# RingEncoder.net
KiCad netlist of a schematic drawn in Altium Designer
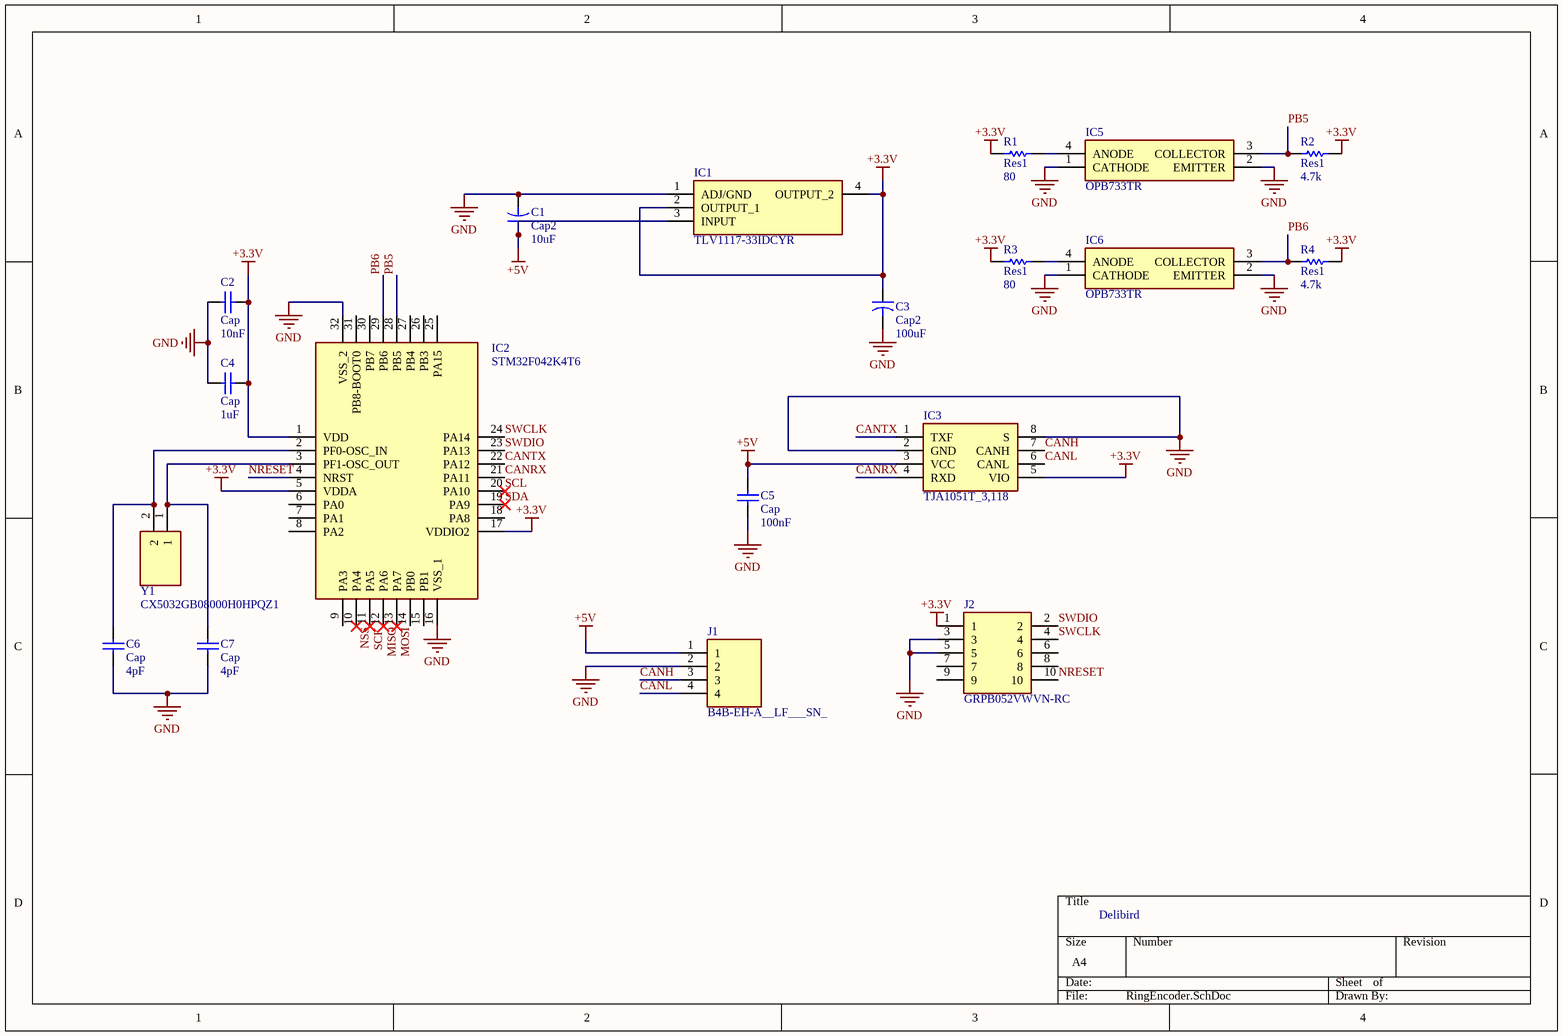
[diagram p0: RingEncoder.SchDoc]

(export (version "E")
  (design (tool "Eeschema 10.0.6"))
  (components
    (comp (ref "C1")
      (value "Cap2")
      (footprint "C0805")
      (description "Capacitor")
      (fields (field (name "ALTIUM_VALUE") "10uF") (field (name "PUBLISHER") "Altium Limited"))
      (libsource (lib "Miscellaneous Devices") (part "Cap2"))
    )
    (comp (ref "C2")
      (value "Cap")
      (footprint "C0805")
      (description "Capacitor")
      (fields (field (name "ALTIUM_VALUE") "10nF") (field (name "PUBLISHER") "Altium Limited"))
      (libsource (lib "Miscellaneous Devices") (part "Cap"))
    )
    (comp (ref "C3")
      (value "Cap2")
      (footprint "C0805")
      (description "Capacitor")
      (fields (field (name "ALTIUM_VALUE") "100uF") (field (name "PUBLISHER") "Altium Limited"))
      (libsource (lib "Miscellaneous Devices") (part "Cap2"))
    )
    (comp (ref "C4")
      (value "Cap")
      (footprint "C0805")
      (description "Capacitor")
      (fields (field (name "ALTIUM_VALUE") "1uF") (field (name "PUBLISHER") "Altium Limited"))
      (libsource (lib "Miscellaneous Devices") (part "Cap"))
    )
    (comp (ref "C5")
      (value "Cap")
      (footprint "C0805")
      (description "Capacitor")
      (fields (field (name "ALTIUM_VALUE") "100nF") (field (name "PUBLISHER") "Altium Limited"))
      (libsource (lib "Miscellaneous Devices") (part "Cap"))
    )
    (comp (ref "C6")
      (value "Cap")
      (footprint "C0805")
      (description "Capacitor")
      (fields (field (name "ALTIUM_VALUE") "4pF") (field (name "PUBLISHER") "Altium Limited"))
      (libsource (lib "Miscellaneous Devices") (part "Cap"))
    )
    (comp (ref "C7")
      (value "Cap")
      (footprint "C0805")
      (description "Capacitor")
      (fields (field (name "ALTIUM_VALUE") "4pF") (field (name "PUBLISHER") "Altium Limited"))
      (libsource (lib "Miscellaneous Devices") (part "Cap"))
    )
    (comp (ref "IC1")
      (value "TLV1117-33IDCYR")
      (footprint "Embedded:SOT230P700X180-4N")
      (description "Integrated Circuit")
      (fields
        (field (name "MANUFACTURER_PART_NUMBER") "TLV1117-33CDCYR")
        (field (name "MOUSER PART NUMBER") "595-TLV1117-33CDCYR")
      )
      (libsource (lib "*") (part "TLV1117-33CDCYR"))
    )
    (comp (ref "IC2")
      (value "STM32F042K4T6")
      (footprint "Embedded:QFP80P900X900X160-32N")
      (description "Integrated Circuit")
      (fields (field (name "MOUSER PART NUMBER") "511-STM32F042K4T6"))
      (libsource (lib "*") (part "STM32F042K4T6"))
    )
    (comp (ref "IC3")
      (value "TJA1051T_3,118")
      (footprint "Embedded:SOIC127P600X175-8N")
      (description "Integrated Circuit")
      (fields
        (field (name "MANUFACTURER_PART_NUMBER") "TJA1051T/3,118")
        (field (name "MOUSER PART NUMBER") "771-TJA1051T3118")
      )
      (libsource (lib "Embedded") (part "TJA1051T_3,118"))
    )
    (comp (ref "IC5")
      (value "OPB733TR")
      (footprint "OPB733TR")
      (description "Integrated Circuit")
      (fields (field (name "MOUSER PART NUMBER") "828-OPB733TR"))
      (libsource (lib "Embedded") (part "OPB733TR"))
    )
    (comp (ref "IC6")
      (value "OPB733TR")
      (footprint "OPB733TR")
      (description "Integrated Circuit")
      (fields (field (name "MOUSER PART NUMBER") "828-OPB733TR"))
      (libsource (lib "Embedded") (part "OPB733TR"))
    )
    (comp (ref "J1")
      (value "B4B-EH-A__LF___SN_")
      (footprint "Embedded:SHDR4W64P0X250_1X4_1250X380X600P")
      (description "Connector")
      (fields (field (name "MANUFACTURER_PART_NUMBER") "B4B-EH-A (LF) (SN)"))
      (libsource (lib "*") (part "B4B-EH-A__LF___SN_"))
    )
    (comp (ref "J2")
      (value "GRPB052VWVN-RC")
      (footprint "Embedded:HDRV10W50P127_2X5_635X340X430P")
      (description "Connector")
      (libsource (lib "Embedded") (part "GRPB052VWVN-RC"))
    )
    (comp (ref "R1")
      (value "Res1")
      (footprint "C0805")
      (description "Resistor")
      (fields (field (name "ALTIUM_VALUE") "80") (field (name "PUBLISHER") "Altium Limited"))
      (libsource (lib "Miscellaneous Devices") (part "Res1"))
    )
    (comp (ref "R2")
      (value "Res1")
      (footprint "C0805")
      (description "Resistor")
      (fields (field (name "ALTIUM_VALUE") "4.7k") (field (name "PUBLISHER") "Altium Limited"))
      (libsource (lib "Miscellaneous Devices") (part "Res1"))
    )
    (comp (ref "R3")
      (value "Res1")
      (footprint "C0805")
      (description "Resistor")
      (fields (field (name "ALTIUM_VALUE") "80") (field (name "PUBLISHER") "Altium Limited"))
      (libsource (lib "Miscellaneous Devices") (part "Res1"))
    )
    (comp (ref "R4")
      (value "Res1")
      (footprint "C0805")
      (description "Resistor")
      (fields (field (name "ALTIUM_VALUE") "4.7k") (field (name "PUBLISHER") "Altium Limited"))
      (libsource (lib "Miscellaneous Devices") (part "Res1"))
    )
    (comp (ref "Y1")
      (value "CX5032GB08000H0HPQZ1")
      (footprint "Embedded:CX5032GB08000H0HPQZ1")
      (description "Crystal or Oscillator")
      (fields (field (name "MOUSER PART NUMBER") "581-CX532GB8HHPQZ1"))
      (libsource (lib "*") (part "CX5032GB08000H0HPQZ1"))
    )
  )
  (nets
    (net (code "1") (name "+3.3V") (class "Default")
      (node (ref "C2") (pin "1") (pinfunction "1_1") (pintype "passive"))
      (node (ref "C3") (pin "1") (pinfunction "1_1") (pintype "passive"))
      (node (ref "C4") (pin "1") (pinfunction "1_1") (pintype "passive"))
      (node (ref "IC1") (pin "2") (pinfunction "OUTPUT_1_2") (pintype "passive"))
      (node (ref "IC1") (pin "4") (pinfunction "OUTPUT_2_4") (pintype "passive"))
      (node (ref "IC2") (pin "1") (pinfunction "VDD_1") (pintype "passive"))
      (node (ref "IC2") (pin "17") (pinfunction "VDDIO2_17") (pintype "passive"))
      (node (ref "IC2") (pin "5") (pinfunction "VDDA_5") (pintype "passive"))
      (node (ref "IC3") (pin "5") (pinfunction "VIO_5") (pintype "passive"))
      (node (ref "J2") (pin "1") (pinfunction "1_1") (pintype "passive"))
      (node (ref "R1") (pin "1") (pinfunction "1_1") (pintype "passive"))
      (node (ref "R2") (pin "2") (pinfunction "2_2") (pintype "passive"))
      (node (ref "R3") (pin "1") (pinfunction "1_1") (pintype "passive"))
      (node (ref "R4") (pin "2") (pinfunction "2_2") (pintype "passive"))
    )
    (net (code "2") (name "+5V") (class "Default")
      (node (ref "C1") (pin "1") (pinfunction "1_1") (pintype "passive"))
      (node (ref "C5") (pin "1") (pinfunction "1_1") (pintype "passive"))
      (node (ref "IC1") (pin "3") (pinfunction "INPUT_3") (pintype "passive"))
      (node (ref "IC3") (pin "3") (pinfunction "VCC_3") (pintype "passive"))
      (node (ref "J1") (pin "1") (pinfunction "1_1") (pintype "passive"))
    )
    (net (code "3") (name "/CANH") (class "Default")
      (node (ref "IC3") (pin "7") (pinfunction "CANH_7") (pintype "passive"))
      (node (ref "J1") (pin "3") (pinfunction "3_3") (pintype "passive"))
    )
    (net (code "4") (name "/CANL") (class "Default")
      (node (ref "IC3") (pin "6") (pinfunction "CANL_6") (pintype "passive"))
      (node (ref "J1") (pin "4") (pinfunction "4_4") (pintype "passive"))
    )
    (net (code "5") (name "/CANRX") (class "Default")
      (node (ref "IC2") (pin "21") (pinfunction "PA11_21") (pintype "passive"))
      (node (ref "IC3") (pin "4") (pinfunction "RXD_4") (pintype "passive"))
    )
    (net (code "6") (name "/CANTX") (class "Default")
      (node (ref "IC2") (pin "22") (pinfunction "PA12_22") (pintype "passive"))
      (node (ref "IC3") (pin "1") (pinfunction "TXF_1") (pintype "passive"))
    )
    (net (code "7") (name "/MISO") (class "Default")
      (node (ref "IC2") (pin "12") (pinfunction "PA6_12") (pintype "passive+no_connect"))
    )
    (net (code "8") (name "/MOSI") (class "Default")
      (node (ref "IC2") (pin "13") (pinfunction "PA7_13") (pintype "passive+no_connect"))
    )
    (net (code "9") (name "/NRESET") (class "Default")
      (node (ref "IC2") (pin "4") (pinfunction "NRST_4") (pintype "passive"))
      (node (ref "J2") (pin "10") (pinfunction "10_10") (pintype "passive"))
    )
    (net (code "10") (name "/NSS") (class "Default")
      (node (ref "IC2") (pin "10") (pinfunction "PA4_10") (pintype "passive+no_connect"))
    )
    (net (code "11") (name "/PB5") (class "Default")
      (node (ref "IC2") (pin "28") (pinfunction "PB5_28") (pintype "passive"))
      (node (ref "IC5") (pin "3") (pinfunction "COLLECTOR_3") (pintype "passive"))
      (node (ref "R2") (pin "1") (pinfunction "1_1") (pintype "passive"))
    )
    (net (code "12") (name "/PB6") (class "Default")
      (node (ref "IC2") (pin "29") (pinfunction "PB6_29") (pintype "passive"))
      (node (ref "IC6") (pin "3") (pinfunction "COLLECTOR_3") (pintype "passive"))
      (node (ref "R4") (pin "1") (pinfunction "1_1") (pintype "passive"))
    )
    (net (code "13") (name "/SCK") (class "Default")
      (node (ref "IC2") (pin "11") (pinfunction "PA5_11") (pintype "passive+no_connect"))
    )
    (net (code "14") (name "/SCL") (class "Default")
      (node (ref "IC2") (pin "20") (pinfunction "PA10_20") (pintype "passive+no_connect"))
    )
    (net (code "15") (name "/SDA") (class "Default")
      (node (ref "IC2") (pin "19") (pinfunction "PA9_19") (pintype "passive+no_connect"))
    )
    (net (code "16") (name "/SWCLK") (class "Default")
      (node (ref "IC2") (pin "24") (pinfunction "PA14_24") (pintype "passive"))
      (node (ref "J2") (pin "4") (pinfunction "4_4") (pintype "passive"))
    )
    (net (code "17") (name "/SWDIO") (class "Default")
      (node (ref "IC2") (pin "23") (pinfunction "PA13_23") (pintype "passive"))
      (node (ref "J2") (pin "2") (pinfunction "2_2") (pintype "passive"))
    )
    (net (code "18") (name "GND") (class "Default")
      (node (ref "C1") (pin "2") (pinfunction "2_2") (pintype "passive"))
      (node (ref "C2") (pin "2") (pinfunction "2_2") (pintype "passive"))
      (node (ref "C3") (pin "2") (pinfunction "2_2") (pintype "passive"))
      (node (ref "C4") (pin "2") (pinfunction "2_2") (pintype "passive"))
      (node (ref "C5") (pin "2") (pinfunction "2_2") (pintype "passive"))
      (node (ref "C6") (pin "1") (pinfunction "1_1") (pintype "passive"))
      (node (ref "C7") (pin "1") (pinfunction "1_1") (pintype "passive"))
      (node (ref "IC1") (pin "1") (pinfunction "ADJ/GND_1") (pintype "passive"))
      (node (ref "IC2") (pin "16") (pinfunction "VSS_1_16") (pintype "passive"))
      (node (ref "IC2") (pin "32") (pinfunction "VSS_2_32") (pintype "passive"))
      (node (ref "IC3") (pin "2") (pinfunction "GND_2") (pintype "passive"))
      (node (ref "IC3") (pin "8") (pinfunction "S_8") (pintype "passive"))
      (node (ref "IC5") (pin "1") (pinfunction "CATHODE_1") (pintype "passive"))
      (node (ref "IC5") (pin "2") (pinfunction "EMITTER_2") (pintype "passive"))
      (node (ref "IC6") (pin "1") (pinfunction "CATHODE_1") (pintype "passive"))
      (node (ref "IC6") (pin "2") (pinfunction "EMITTER_2") (pintype "passive"))
      (node (ref "J1") (pin "2") (pinfunction "2_2") (pintype "passive"))
      (node (ref "J2") (pin "3") (pinfunction "3_3") (pintype "passive"))
      (node (ref "J2") (pin "5") (pinfunction "5_5") (pintype "passive"))
    )
    (net (code "19") (name "Net-(IC2-PF0-OSC_IN)") (class "Default")
      (node (ref "C6") (pin "2") (pinfunction "2_2") (pintype "passive"))
      (node (ref "IC2") (pin "2") (pinfunction "PF0-OSC_IN_2") (pintype "passive"))
      (node (ref "Y1") (pin "2") (pinfunction "2_2") (pintype "passive"))
    )
    (net (code "20") (name "Net-(IC2-PF1-OSC_OUT)") (class "Default")
      (node (ref "C7") (pin "2") (pinfunction "2_2") (pintype "passive"))
      (node (ref "IC2") (pin "3") (pinfunction "PF1-OSC_OUT_3") (pintype "passive"))
      (node (ref "Y1") (pin "1") (pinfunction "1_1") (pintype "passive"))
    )
    (net (code "21") (name "Net-(IC5-ANODE)") (class "Default")
      (node (ref "IC5") (pin "4") (pinfunction "ANODE_4") (pintype "passive"))
      (node (ref "R1") (pin "2") (pinfunction "2_2") (pintype "passive"))
    )
    (net (code "22") (name "Net-(IC6-ANODE)") (class "Default")
      (node (ref "IC6") (pin "4") (pinfunction "ANODE_4") (pintype "passive"))
      (node (ref "R3") (pin "2") (pinfunction "2_2") (pintype "passive"))
    )
    (net (code "23") (name "unconnected-(IC2-PA0-Pad6)") (class "Default")
      (node (ref "IC2") (pin "6") (pinfunction "PA0_6") (pintype "passive"))
    )
    (net (code "24") (name "unconnected-(IC2-PA1-Pad7)") (class "Default")
      (node (ref "IC2") (pin "7") (pinfunction "PA1_7") (pintype "passive"))
    )
    (net (code "25") (name "unconnected-(IC2-PA2-Pad8)") (class "Default")
      (node (ref "IC2") (pin "8") (pinfunction "PA2_8") (pintype "passive"))
    )
    (net (code "26") (name "unconnected-(IC2-PA3-Pad9)") (class "Default")
      (node (ref "IC2") (pin "9") (pinfunction "PA3_9") (pintype "passive"))
    )
    (net (code "27") (name "unconnected-(IC2-PA8-Pad18)") (class "Default")
      (node (ref "IC2") (pin "18") (pinfunction "PA8_18") (pintype "passive"))
    )
    (net (code "28") (name "unconnected-(IC2-PA15-Pad25)") (class "Default")
      (node (ref "IC2") (pin "25") (pinfunction "PA15_25") (pintype "passive"))
    )
    (net (code "29") (name "unconnected-(IC2-PB0-Pad14)") (class "Default")
      (node (ref "IC2") (pin "14") (pinfunction "PB0_14") (pintype "passive"))
    )
    (net (code "30") (name "unconnected-(IC2-PB1-Pad15)") (class "Default")
      (node (ref "IC2") (pin "15") (pinfunction "PB1_15") (pintype "passive"))
    )
    (net (code "31") (name "unconnected-(IC2-PB3-Pad26)") (class "Default")
      (node (ref "IC2") (pin "26") (pinfunction "PB3_26") (pintype "passive"))
    )
    (net (code "32") (name "unconnected-(IC2-PB4-Pad27)") (class "Default")
      (node (ref "IC2") (pin "27") (pinfunction "PB4_27") (pintype "passive"))
    )
    (net (code "33") (name "unconnected-(IC2-PB7-Pad30)") (class "Default")
      (node (ref "IC2") (pin "30") (pinfunction "PB7_30") (pintype "passive"))
    )
    (net (code "34") (name "unconnected-(IC2-PB8-BOOT0-Pad31)") (class "Default")
      (node (ref "IC2") (pin "31") (pinfunction "PB8-BOOT0_31") (pintype "passive"))
    )
    (net (code "35") (name "unconnected-(J2-Pad6)") (class "Default")
      (node (ref "J2") (pin "6") (pinfunction "6_6") (pintype "passive"))
    )
    (net (code "36") (name "unconnected-(J2-Pad7)") (class "Default")
      (node (ref "J2") (pin "7") (pinfunction "7_7") (pintype "passive"))
    )
    (net (code "37") (name "unconnected-(J2-Pad8)") (class "Default")
      (node (ref "J2") (pin "8") (pinfunction "8_8") (pintype "passive"))
    )
    (net (code "38") (name "unconnected-(J2-Pad9)") (class "Default")
      (node (ref "J2") (pin "9") (pinfunction "9_9") (pintype "passive"))
    )
  )
)
